# IMU.net
KiCad netlist of a schematic drawn in Altium Designer
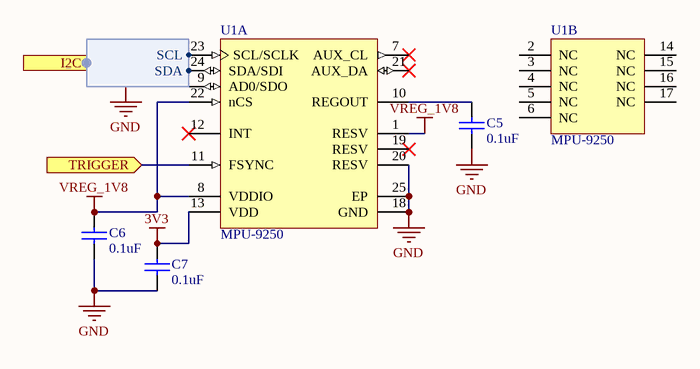
[diagram p0: IMU.SchDoc]

(export (version "E")
  (design (tool "Eeschema 10.0.6"))
  (components
    (comp (ref "C5")
      (value "0.1uF")
      (footprint "C0402[1005X55]")
      (description "0.1uF 6.3V 10% 0402 (1005 Metric)")
      (fields (field (name "PARTNUMBER") "GRM155R70J104KA01D") (field (name "MANUFACTURER") "Murata"))
      (libsource (lib "Capacitors") (part "CAP_0.1uF_6.3V_0402_10%"))
    )
    (comp (ref "C6")
      (value "0.1uF")
      (footprint "C0402[1005X55]")
      (description "0.1uF 6.3V 10% 0402 (1005 Metric)")
      (fields (field (name "PARTNUMBER") "GRM155R70J104KA01D") (field (name "MANUFACTURER") "Murata"))
      (libsource (lib "Capacitors") (part "CAP_0.1uF_6.3V_0402_10%"))
    )
    (comp (ref "C7")
      (value "0.1uF")
      (footprint "C0402[1005X55]")
      (description "0.1uF 6.3V 10% 0402 (1005 Metric)")
      (fields (field (name "PARTNUMBER") "GRM155R70J104KA01D") (field (name "MANUFACTURER") "Murata"))
      (libsource (lib "Capacitors") (part "CAP_0.1uF_6.3V_0402_10%"))
    )
    (comp (ref "U1")
      (value "MPU-9250")
      (footprint "QFN-24 (0.4MM)")
      (fields (field (name "MANUFACTURER") "Invensense"))
      (libsource (lib "ICs") (part "MPU-9250"))
    )
  )
  (nets
    (net (code "2") (name "/SCL") (class "Default")
      (node (ref "U1") (pin "23") (pinfunction "SCL/SCLK_23") (pintype "input"))
    )
    (net (code "3") (name "/SDA") (class "Default")
      (node (ref "U1") (pin "24") (pinfunction "SDA/SDI_24") (pintype "bidirectional"))
    )
    (net (code "4") (name "/TRIGGER") (class "Default")
      (node (ref "U1") (pin "11") (pinfunction "FSYNC_11") (pintype "input"))
    )
    (net (code "6") (name "3V3") (class "Default")
      (node (ref "C7") (pin "2") (pinfunction "2_2") (pintype "passive"))
      (node (ref "U1") (pin "13") (pinfunction "VDD_13") (pintype "power_in"))
    )
    (net (code "7") (name "GND") (class "Default")
      (node (ref "C5") (pin "1") (pinfunction "1_1") (pintype "passive"))
      (node (ref "C6") (pin "1") (pinfunction "1_1") (pintype "passive"))
      (node (ref "C7") (pin "1") (pinfunction "1_1") (pintype "passive"))
      (node (ref "U1") (pin "18") (pinfunction "GND_18") (pintype "power_in"))
      (node (ref "U1") (pin "20") (pinfunction "RESV_20") (pintype "power_in"))
      (node (ref "U1") (pin "25") (pinfunction "EP_25") (pintype "passive"))
      (node (ref "U1") (pin "9") (pinfunction "AD0/SDO_9") (pintype "bidirectional"))
    )
    (net (code "8") (name "Net-(U1A-REGOUT)") (class "Default")
      (node (ref "C5") (pin "2") (pinfunction "2_2") (pintype "passive"))
      (node (ref "U1") (pin "10") (pinfunction "REGOUT_10") (pintype "passive"))
    )
    (net (code "9") (name "VREG_1V8") (class "Default")
      (node (ref "C6") (pin "2") (pinfunction "2_2") (pintype "passive"))
      (node (ref "U1") (pin "1") (pinfunction "RESV_1") (pintype "power_in"))
      (node (ref "U1") (pin "22") (pinfunction "nCS_22") (pintype "input"))
      (node (ref "U1") (pin "8") (pinfunction "VDDIO_8") (pintype "power_in"))
    )
    (net (code "10") (name "unconnected-(U1A-AUX_CL-Pad7)") (class "Default")
      (node (ref "U1") (pin "7") (pinfunction "AUX_CL_7") (pintype "output+no_connect"))
    )
    (net (code "11") (name "unconnected-(U1A-AUX_DA-Pad21)") (class "Default")
      (node (ref "U1") (pin "21") (pinfunction "AUX_DA_21") (pintype "bidirectional+no_connect"))
    )
    (net (code "12") (name "unconnected-(U1A-INT-Pad12)") (class "Default")
      (node (ref "U1") (pin "12") (pinfunction "INT_12") (pintype "tri_state+no_connect"))
    )
    (net (code "13") (name "unconnected-(U1A-RESV-Pad19)") (class "Default")
      (node (ref "U1") (pin "19") (pinfunction "RESV_19") (pintype "passive+no_connect"))
    )
    (net (code "14") (name "unconnected-(U1B-NC-Pad2)") (class "Default")
      (node (ref "U1") (pin "2") (pinfunction "NC_2") (pintype "passive"))
    )
    (net (code "15") (name "unconnected-(U1B-NC-Pad3)") (class "Default")
      (node (ref "U1") (pin "3") (pinfunction "NC_3") (pintype "passive"))
    )
    (net (code "16") (name "unconnected-(U1B-NC-Pad4)") (class "Default")
      (node (ref "U1") (pin "4") (pinfunction "NC_4") (pintype "passive"))
    )
    (net (code "17") (name "unconnected-(U1B-NC-Pad5)") (class "Default")
      (node (ref "U1") (pin "5") (pinfunction "NC_5") (pintype "passive"))
    )
    (net (code "18") (name "unconnected-(U1B-NC-Pad6)") (class "Default")
      (node (ref "U1") (pin "6") (pinfunction "NC_6") (pintype "passive"))
    )
    (net (code "19") (name "unconnected-(U1B-NC-Pad14)") (class "Default")
      (node (ref "U1") (pin "14") (pinfunction "NC_14") (pintype "passive"))
    )
    (net (code "20") (name "unconnected-(U1B-NC-Pad15)") (class "Default")
      (node (ref "U1") (pin "15") (pinfunction "NC_15") (pintype "passive"))
    )
    (net (code "21") (name "unconnected-(U1B-NC-Pad16)") (class "Default")
      (node (ref "U1") (pin "16") (pinfunction "NC_16") (pintype "passive"))
    )
    (net (code "22") (name "unconnected-(U1B-NC-Pad17)") (class "Default")
      (node (ref "U1") (pin "17") (pinfunction "NC_17") (pintype "passive"))
    )
  )
)
